# copycat_atten.net
KiCad netlist of a schematic drawn in EAGLE
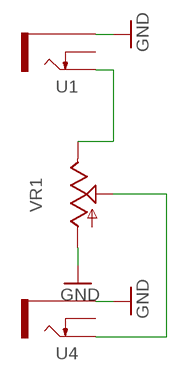
[diagram p0: schematic, sheet 1]

(export (version "E")
  (design (tool "Eeschema 10.0.6"))
  (components
    (comp (ref "U1")
      (value "THONKICONNNEW")
      (footprint "eagle-import:WQP-PJ301M-12_JACK")
      (libsource (lib "eagle-import") (part "THONKICONNNEW"))
    )
    (comp (ref "U4")
      (value "THONKICONNNEW")
      (footprint "eagle-import:WQP-PJ301M-12_JACK")
      (libsource (lib "eagle-import") (part "THONKICONNNEW"))
    )
    (comp (ref "VR1")
      (value "9MM_SNAP-IN_POT_")
      (footprint "eagle-import:9MM_SNAP-IN_POT")
      (libsource (lib "eagle-import") (part "9MM_SNAP-IN_POT_"))
    )
  )
  (nets
    (net (code "1") (name "GND") (class "Default")
      (node (ref "U1") (pin "P$3_SLEEVE") (pinfunction "SLEEVE_P$3_SLEEVE") (pintype "passive"))
      (node (ref "U4") (pin "P$3_SLEEVE") (pinfunction "SLEEVE_P$3_SLEEVE") (pintype "passive"))
      (node (ref "VR1") (pin "1") (pinfunction "A_1") (pintype "passive"))
    )
    (net (code "2") (name "Net-(U1-TIP)") (class "Default")
      (node (ref "U1") (pin "P$1_TIP") (pinfunction "TIP_P$1_TIP") (pintype "passive"))
      (node (ref "VR1") (pin "3") (pinfunction "E_3") (pintype "passive"))
    )
    (net (code "3") (name "Net-(U4-TIP)") (class "Default")
      (node (ref "U4") (pin "P$1_TIP") (pinfunction "TIP_P$1_TIP") (pintype "passive"))
      (node (ref "VR1") (pin "2") (pinfunction "S_2") (pintype "passive"))
    )
    (net (code "4") (name "unconnected-(U1-SWITCH-PadP$2_SWITCH)") (class "Default")
      (node (ref "U1") (pin "P$2_SWITCH") (pinfunction "SWITCH_P$2_SWITCH") (pintype "passive"))
    )
    (net (code "5") (name "unconnected-(U4-SWITCH-PadP$2_SWITCH)") (class "Default")
      (node (ref "U4") (pin "P$2_SWITCH") (pinfunction "SWITCH_P$2_SWITCH") (pintype "passive"))
    )
  )
)
